# POWER.net
KiCad netlist of a schematic drawn in Altium Designer
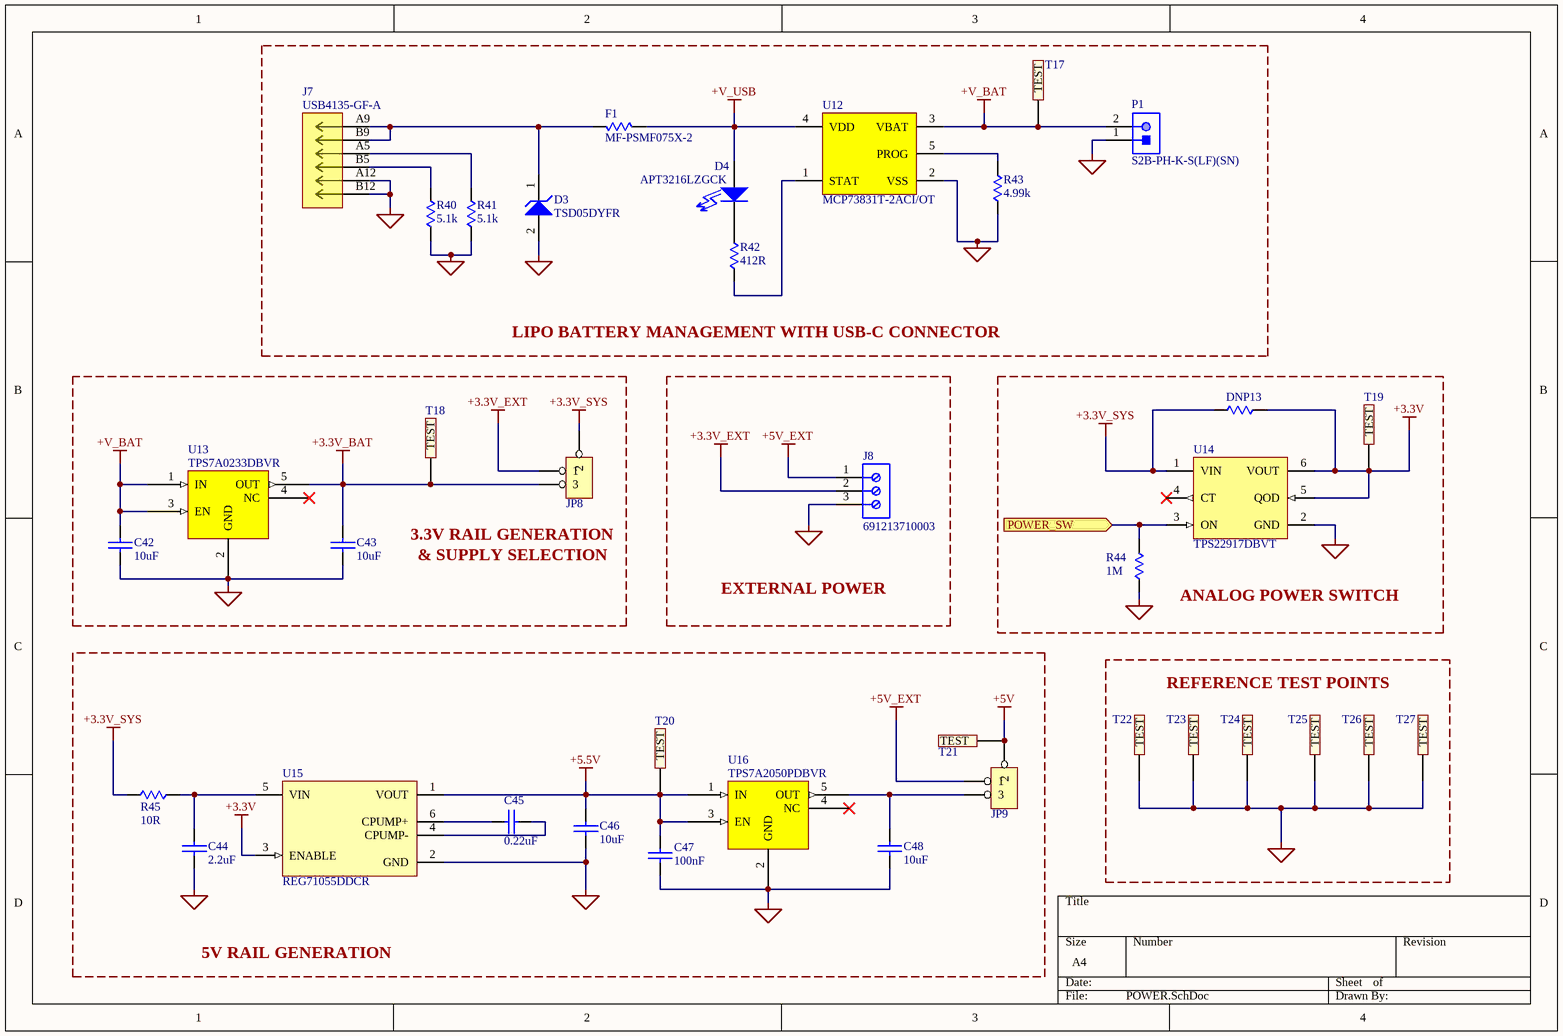
[diagram p0: POWER.SchDoc]

(export (version "E")
  (design (tool "Eeschema 10.0.6"))
  (components
    (comp (ref "C42")
      (value "10uF")
      (footprint "0603-CAP")
      (description "CAP CER 10uF 6.3V X5R 0603")
      (libsource (lib "SGL_Capacitors") (part "Capacitor"))
    )
    (comp (ref "C43")
      (value "10uF")
      (footprint "0603-CAP")
      (description "CAP CER 10uF 6.3V X5R 0603")
      (libsource (lib "SGL_Capacitors") (part "Capacitor"))
    )
    (comp (ref "C44")
      (value "2.2uF")
      (footprint "0603-CAP")
      (description "CAP CER 2.2UF 35V X5R 0603")
      (libsource (lib "SGL_Capacitors") (part "Capacitor"))
    )
    (comp (ref "C45")
      (value "0.22uF")
      (footprint "0603-CAP")
      (description "CAP CER 0.22UF 25V X7R 0603")
      (libsource (lib "SGL_Capacitors") (part "Capacitor"))
    )
    (comp (ref "C46")
      (value "10uF")
      (footprint "0603-CAP")
      (description "CAP CER 10uF 6.3V X5R 0603")
      (libsource (lib "SGL_Capacitors") (part "Capacitor"))
    )
    (comp (ref "C47")
      (value "100nF")
      (footprint "0603-CAP")
      (description "CAP CER 100 NF 50V X7R 0603")
      (libsource (lib "SGL_Capacitors") (part "Capacitor"))
    )
    (comp (ref "C48")
      (value "10uF")
      (footprint "0603-CAP")
      (description "CAP CER 10uF 6.3V X5R 0603")
      (libsource (lib "SGL_Capacitors") (part "Capacitor"))
    )
    (comp (ref "D3")
      (value "TSD05DYFR")
      (footprint "TVS_SOD2_DYF_TEX-L")
      (description "5-V 60-A Unidirectional surge protection device 2-SOT -40 to 125")
      (fields (field (name "COPYRIGHT") "Copyright (C) 2026 Ultra Librarian. All rights reserved."))
      (libsource (lib "BioZ") (part "TSD05DYFR"))
    )
    (comp (ref "D4")
      (value "APT3216LZGCK")
      (footprint "1206-LED")
      (description "LED GREEN CLEAR 2SMD")
      (libsource (lib "SGL_Diodes") (part "LED"))
    )
    (comp (ref "DNP13")
      (value "DNP")
      (footprint "0603-RES")
      (description "RES SMD 5.1K OHM 0.1% 1/10W 0603")
      (libsource (lib "SGL_Resistives") (part "RESISTOR"))
    )
    (comp (ref "F1")
      (value "MF-PSMF075X-2")
      (footprint "0805-RES")
      (description "PTC RESET FUSE 6V 750MA 0805")
      (libsource (lib "SGL_Resistives") (part "RESISTOR"))
    )
    (comp (ref "J7")
      (value "USB4135-GF-A")
      (footprint "CONN_USB4135-GF-A_GCT")
      (description "Description")
      (fields (field (name "COPYRIGHT") "Copyright (C) 2026 Ultra Librarian. All rights reserved."))
      (libsource (lib "BioZ") (part "USB4135-GF-A"))
    )
    (comp (ref "J8")
      (value "691213710003")
      (footprint "691213710003")
      (description "213 Series 5MM Pitch Straight, Pcb Terminal Block, Through Hole, 3 Way")
      (fields (field (name "VOLTAGE") "300V"))
      (libsource (lib "Altium Content Vault") (part "TBL - 1R - 03P - Screw"))
    )
    (comp (ref "JP8")
      (value "JUMPER1X3")
      (footprint "JUMPER3")
      (description "CONN HEADER VERT 36POS 2.54MM")
      (libsource (lib "SGL_Connectors") (part "JUMPER1X3"))
    )
    (comp (ref "JP9")
      (value "JUMPER1X3")
      (footprint "JUMPER3")
      (description "CONN HEADER VERT 36POS 2.54MM")
      (libsource (lib "SGL_Connectors") (part "JUMPER1X3"))
    )
    (comp (ref "P1")
      (value "S2B-PH-K-S(LF)(SN)")
      (footprint "JST-S2B-PH-K-S_V")
      (fields (field (name "TOLERANCE") "20%"))
      (libsource (lib "Altium Content Vault") (part "CN-1P-M-R2"))
    )
    (comp (ref "R40")
      (value "5.1k")
      (footprint "0603-RES")
      (description "RES SMD 5.1K OHM 0.1% 1/10W 0603")
      (libsource (lib "SGL_Resistives") (part "RESISTOR"))
    )
    (comp (ref "R41")
      (value "5.1k")
      (footprint "0603-RES")
      (description "RES SMD 5.1K OHM 0.1% 1/10W 0603")
      (libsource (lib "SGL_Resistives") (part "RESISTOR"))
    )
    (comp (ref "R42")
      (value "412R")
      (footprint "0603-RES")
      (description "RES SMD 412OHM 0.1% 1/10W 0603")
      (libsource (lib "SGL_Resistives") (part "RESISTOR"))
    )
    (comp (ref "R43")
      (value "4.99k")
      (footprint "0603-RES")
      (description "RES SMD 4.99KOHM 0.1% 1/10W 0603")
      (libsource (lib "SGL_Resistives") (part "RESISTOR"))
    )
    (comp (ref "R44")
      (value "1M")
      (footprint "0603-RES")
      (description "RES SMD 1MOHM 0.1% 1/10W 0603")
      (libsource (lib "SGL_Resistives") (part "RESISTOR"))
    )
    (comp (ref "R45")
      (value "10R")
      (footprint "0603-RES")
      (description "RES SMD 10OHM 0.05% 1/10W 0603")
      (libsource (lib "SGL_Resistives") (part "RESISTOR"))
    )
    (comp (ref "T17")
      (value "5002K")
      (footprint "TESTPOINT White")
      (description "PC TEST POINT MINIATURE WHITE")
      (libsource (lib "SGL_Connectors") (part "Testpoint white"))
    )
    (comp (ref "T18")
      (value "5002K")
      (footprint "TESTPOINT White")
      (description "PC TEST POINT MINIATURE WHITE")
      (libsource (lib "SGL_Connectors") (part "Testpoint white"))
    )
    (comp (ref "T19")
      (value "5002K")
      (footprint "TESTPOINT White")
      (description "PC TEST POINT MINIATURE WHITE")
      (libsource (lib "SGL_Connectors") (part "Testpoint white"))
    )
    (comp (ref "T20")
      (value "5002K")
      (footprint "TESTPOINT White")
      (description "PC TEST POINT MINIATURE WHITE")
      (libsource (lib "SGL_Connectors") (part "Testpoint white"))
    )
    (comp (ref "T21")
      (value "5002K")
      (footprint "TESTPOINT White")
      (description "PC TEST POINT MINIATURE WHITE")
      (libsource (lib "") (part "Testpoint white_1"))
    )
    (comp (ref "T22")
      (value "5011K")
      (footprint "TESTPOINT Black")
      (description "PC TEST POINT MULTIPURPOSE BLACK")
      (libsource (lib "SGL_Connectors") (part "Testpoint black"))
    )
    (comp (ref "T23")
      (value "5011K")
      (footprint "TESTPOINT Black")
      (description "PC TEST POINT MULTIPURPOSE BLACK")
      (libsource (lib "SGL_Connectors") (part "Testpoint black"))
    )
    (comp (ref "T24")
      (value "5011K")
      (footprint "TESTPOINT Black")
      (description "PC TEST POINT MULTIPURPOSE BLACK")
      (libsource (lib "SGL_Connectors") (part "Testpoint black"))
    )
    (comp (ref "T25")
      (value "5011K")
      (footprint "TESTPOINT Black")
      (description "PC TEST POINT MULTIPURPOSE BLACK")
      (libsource (lib "SGL_Connectors") (part "Testpoint black"))
    )
    (comp (ref "T26")
      (value "5011K")
      (footprint "TESTPOINT Black")
      (description "PC TEST POINT MULTIPURPOSE BLACK")
      (libsource (lib "SGL_Connectors") (part "Testpoint black"))
    )
    (comp (ref "T27")
      (value "5011K")
      (footprint "TESTPOINT Black")
      (description "PC TEST POINT MULTIPURPOSE BLACK")
      (libsource (lib "SGL_Connectors") (part "Testpoint black"))
    )
    (comp (ref "U12")
      (value "MCP73831T-2ACI/OT")
      (footprint "SOT23_DBV_TEX-M")
      (description "IC CONTROLLR LI-ION 4.2V SOT23-5")
      (libsource (lib "BioZ") (part "CMP-0133-00143-2"))
    )
    (comp (ref "U13")
      (value "TPS7A0233DBVR")
      (footprint "SOT23_DBV_TEX-M")
      (description "200mA, nanopower-IQ (25 nA), low-dropout (LDO) voltage regulator with enable 5-SOT-23 -40 to 125")
      (fields
        (field (name "MANUFACTURER_PART_NUMBER") "TPS7A0230PDBVR")
        (field (name "COPYRIGHT") "Copyright (C) 2026 Ultra Librarian. All rights reserved.")
      )
      (libsource (lib "BioZ") (part "TPS7A0230PDBVR"))
    )
    (comp (ref "U14")
      (value "TPS22917DBVT")
      (footprint "DBV0006_N")
      (fields (field (name "COPYRIGHT") "Copyright (C) 2026 Ultra Librarian. All rights reserved."))
      (libsource (lib "BioZ") (part "TPS22917DBVT"))
    )
    (comp (ref "U15")
      (value "REG71055DDCR")
      (footprint "DDC0006A_M")
      (fields (field (name "MANUFACTURER") "Texas Instruments"))
      (libsource (lib "Altium Content Vault") (part "TI-REG710XX-6_A"))
    )
    (comp (ref "U16")
      (value "TPS7A2050PDBVR")
      (footprint "SOT23_DBV_TEX-M")
      (description "200mA, nanopower-IQ (25 nA), low-dropout (LDO) voltage regulator with enable 5-SOT-23 -40 to 125")
      (fields
        (field (name "MANUFACTURER_PART_NUMBER") "TPS7A0230PDBVR")
        (field (name "COPYRIGHT") "Copyright (C) 2026 Ultra Librarian. All rights reserved.")
      )
      (libsource (lib "BioZ") (part "TPS7A0230PDBVR"))
    )
  )
  (nets
    (net (code "1") (name "+3.3V") (class "Default")
      (node (ref "DNP13") (pin "2") (pinfunction "2_2") (pintype "passive"))
      (node (ref "T19") (pin "1") (pinfunction "TEST_1") (pintype "passive"))
      (node (ref "U14") (pin "5") (pinfunction "QOD_5") (pintype "input"))
      (node (ref "U14") (pin "6") (pinfunction "VOUT_6") (pintype "power_in"))
      (node (ref "U15") (pin "3") (pinfunction "ENABLE_3") (pintype "input"))
    )
    (net (code "2") (name "+3.3V_BAT") (class "Default")
      (node (ref "C43") (pin "1") (pinfunction "1_1") (pintype "passive"))
      (node (ref "JP8") (pin "3") (pinfunction "3_3") (pintype "passive"))
      (node (ref "T18") (pin "1") (pinfunction "TEST_1") (pintype "passive"))
      (node (ref "U13") (pin "5") (pinfunction "OUT_5") (pintype "output"))
    )
    (net (code "3") (name "+3.3V_EXT") (class "Default")
      (node (ref "J8") (pin "2") (pinfunction "2_2") (pintype "passive"))
      (node (ref "JP8") (pin "1") (pinfunction "1_1") (pintype "passive"))
    )
    (net (code "4") (name "+3.3V_SYS") (class "Default")
      (node (ref "DNP13") (pin "1") (pinfunction "1_1") (pintype "passive"))
      (node (ref "JP8") (pin "2") (pinfunction "2_2") (pintype "passive"))
      (node (ref "R45") (pin "1") (pinfunction "1_1") (pintype "passive"))
      (node (ref "U14") (pin "1") (pinfunction "VIN_1") (pintype "power_in"))
    )
    (net (code "5") (name "+5.5V") (class "Default")
      (node (ref "C46") (pin "1") (pinfunction "1_1") (pintype "passive"))
      (node (ref "C47") (pin "1") (pinfunction "1_1") (pintype "passive"))
      (node (ref "T20") (pin "1") (pinfunction "TEST_1") (pintype "passive"))
      (node (ref "U15") (pin "1") (pinfunction "VOUT_1") (pintype "power_in"))
      (node (ref "U16") (pin "1") (pinfunction "IN_1") (pintype "input"))
      (node (ref "U16") (pin "3") (pinfunction "EN_3") (pintype "input"))
    )
    (net (code "6") (name "+5V") (class "Default")
      (node (ref "JP9") (pin "2") (pinfunction "2_2") (pintype "passive"))
      (node (ref "T21") (pin "1") (pinfunction "TEST_1") (pintype "passive"))
    )
    (net (code "7") (name "+5V_EXT") (class "Default")
      (node (ref "J8") (pin "1") (pinfunction "1_1") (pintype "passive"))
      (node (ref "JP9") (pin "1") (pinfunction "1_1") (pintype "passive"))
    )
    (net (code "8") (name "+V_BAT") (class "Default")
      (node (ref "C42") (pin "1") (pinfunction "1_1") (pintype "passive"))
      (node (ref "P1") (pin "2") (pinfunction "2_2") (pintype "passive"))
      (node (ref "T17") (pin "1") (pinfunction "TEST_1") (pintype "passive"))
      (node (ref "U12") (pin "3") (pinfunction "VBAT_3") (pintype "power_in"))
      (node (ref "U13") (pin "1") (pinfunction "IN_1") (pintype "input"))
      (node (ref "U13") (pin "3") (pinfunction "EN_3") (pintype "input"))
    )
    (net (code "9") (name "+V_USB") (class "Default")
      (node (ref "D4") (pin "1") (pinfunction "1_1") (pintype "passive"))
      (node (ref "F1") (pin "2") (pinfunction "2_2") (pintype "passive"))
      (node (ref "U12") (pin "4") (pinfunction "VDD_4") (pintype "power_in"))
    )
    (net (code "10") (name "/POWER_SW") (class "Default")
      (node (ref "R44") (pin "2") (pinfunction "2_2") (pintype "passive"))
      (node (ref "U14") (pin "3") (pinfunction "ON_3") (pintype "input"))
    )
    (net (code "11") (name "GND") (class "Default")
      (node (ref "C42") (pin "2") (pinfunction "2_2") (pintype "passive"))
      (node (ref "C43") (pin "2") (pinfunction "2_2") (pintype "passive"))
      (node (ref "C44") (pin "1") (pinfunction "1_1") (pintype "passive"))
      (node (ref "C46") (pin "2") (pinfunction "2_2") (pintype "passive"))
      (node (ref "C47") (pin "2") (pinfunction "2_2") (pintype "passive"))
      (node (ref "C48") (pin "2") (pinfunction "2_2") (pintype "passive"))
      (node (ref "D3") (pin "2") (pinfunction "A_2") (pintype "passive"))
      (node (ref "J7") (pin "A12") (pinfunction "GND_A12") (pintype "power_in"))
      (node (ref "J7") (pin "B12") (pinfunction "GND_B12") (pintype "power_in"))
      (node (ref "J8") (pin "3") (pinfunction "3_3") (pintype "passive"))
      (node (ref "P1") (pin "1") (pinfunction "1_1") (pintype "passive"))
      (node (ref "R40") (pin "2") (pinfunction "2_2") (pintype "passive"))
      (node (ref "R41") (pin "2") (pinfunction "2_2") (pintype "passive"))
      (node (ref "R43") (pin "1") (pinfunction "1_1") (pintype "passive"))
      (node (ref "R44") (pin "1") (pinfunction "1_1") (pintype "passive"))
      (node (ref "T22") (pin "1") (pinfunction "TEST_1") (pintype "passive"))
      (node (ref "T23") (pin "1") (pinfunction "TEST_1") (pintype "passive"))
      (node (ref "T24") (pin "1") (pinfunction "TEST_1") (pintype "passive"))
      (node (ref "T25") (pin "1") (pinfunction "TEST_1") (pintype "passive"))
      (node (ref "T26") (pin "1") (pinfunction "TEST_1") (pintype "passive"))
      (node (ref "T27") (pin "1") (pinfunction "TEST_1") (pintype "passive"))
      (node (ref "U12") (pin "2") (pinfunction "VSS_2") (pintype "power_in"))
      (node (ref "U13") (pin "2") (pinfunction "GND_2") (pintype "power_in"))
      (node (ref "U14") (pin "2") (pinfunction "GND_2") (pintype "power_in"))
      (node (ref "U15") (pin "2") (pinfunction "GND_2") (pintype "power_in"))
      (node (ref "U16") (pin "2") (pinfunction "GND_2") (pintype "power_in"))
    )
    (net (code "12") (name "Net-(D3-K)") (class "Default")
      (node (ref "D3") (pin "1") (pinfunction "K_1") (pintype "passive"))
      (node (ref "F1") (pin "1") (pinfunction "1_1") (pintype "passive"))
      (node (ref "J7") (pin "A9") (pinfunction "VBUS_A9") (pintype "passive"))
      (node (ref "J7") (pin "B9") (pinfunction "VBUS_B9") (pintype "passive"))
    )
    (net (code "13") (name "Net-(D4-Pad2)") (class "Default")
      (node (ref "D4") (pin "2") (pinfunction "2_2") (pintype "passive"))
      (node (ref "R42") (pin "2") (pinfunction "2_2") (pintype "passive"))
    )
    (net (code "14") (name "Net-(J7-CC1)") (class "Default")
      (node (ref "J7") (pin "A5") (pinfunction "CC1_A5") (pintype "passive"))
      (node (ref "R41") (pin "1") (pinfunction "1_1") (pintype "passive"))
    )
    (net (code "15") (name "Net-(J7-CC2)") (class "Default")
      (node (ref "J7") (pin "B5") (pinfunction "CC2_B5") (pintype "passive"))
      (node (ref "R40") (pin "1") (pinfunction "1_1") (pintype "passive"))
    )
    (net (code "16") (name "Net-(U12-PROG)") (class "Default")
      (node (ref "R43") (pin "2") (pinfunction "2_2") (pintype "passive"))
      (node (ref "U12") (pin "5") (pinfunction "PROG_5") (pintype "passive"))
    )
    (net (code "17") (name "Net-(U12-STAT)") (class "Default")
      (node (ref "R42") (pin "1") (pinfunction "1_1") (pintype "passive"))
      (node (ref "U12") (pin "1") (pinfunction "STAT_1") (pintype "passive"))
    )
    (net (code "18") (name "Net-(U15-CPUMP+)") (class "Default")
      (node (ref "C45") (pin "1") (pinfunction "1_1") (pintype "passive"))
      (node (ref "U15") (pin "6") (pinfunction "CPUMP+_6") (pintype "passive"))
    )
    (net (code "19") (name "Net-(U15-CPUMP-)") (class "Default")
      (node (ref "C45") (pin "2") (pinfunction "2_2") (pintype "passive"))
      (node (ref "U15") (pin "4") (pinfunction "CPUMP-_4") (pintype "passive"))
    )
    (net (code "20") (name "Net-(U15-VIN)") (class "Default")
      (node (ref "C44") (pin "2") (pinfunction "2_2") (pintype "passive"))
      (node (ref "R45") (pin "2") (pinfunction "2_2") (pintype "passive"))
      (node (ref "U15") (pin "5") (pinfunction "VIN_5") (pintype "power_in"))
    )
    (net (code "21") (name "Net-(U16-OUT)") (class "Default")
      (node (ref "C48") (pin "1") (pinfunction "1_1") (pintype "passive"))
      (node (ref "JP9") (pin "3") (pinfunction "3_3") (pintype "passive"))
      (node (ref "U16") (pin "5") (pinfunction "OUT_5") (pintype "output"))
    )
    (net (code "22") (name "unconnected-(U13-NC-Pad4)") (class "Default")
      (node (ref "U13") (pin "4") (pinfunction "NC_4") (pintype "passive+no_connect"))
    )
    (net (code "23") (name "unconnected-(U14-CT-Pad4)") (class "Default")
      (node (ref "U14") (pin "4") (pinfunction "CT_4") (pintype "output+no_connect"))
    )
    (net (code "24") (name "unconnected-(U16-NC-Pad4)") (class "Default")
      (node (ref "U16") (pin "4") (pinfunction "NC_4") (pintype "passive+no_connect"))
    )
  )
)
